# TY_FC_CONTRAL_9.net
KiCad netlist of a schematic drawn in EasyEDA Pro
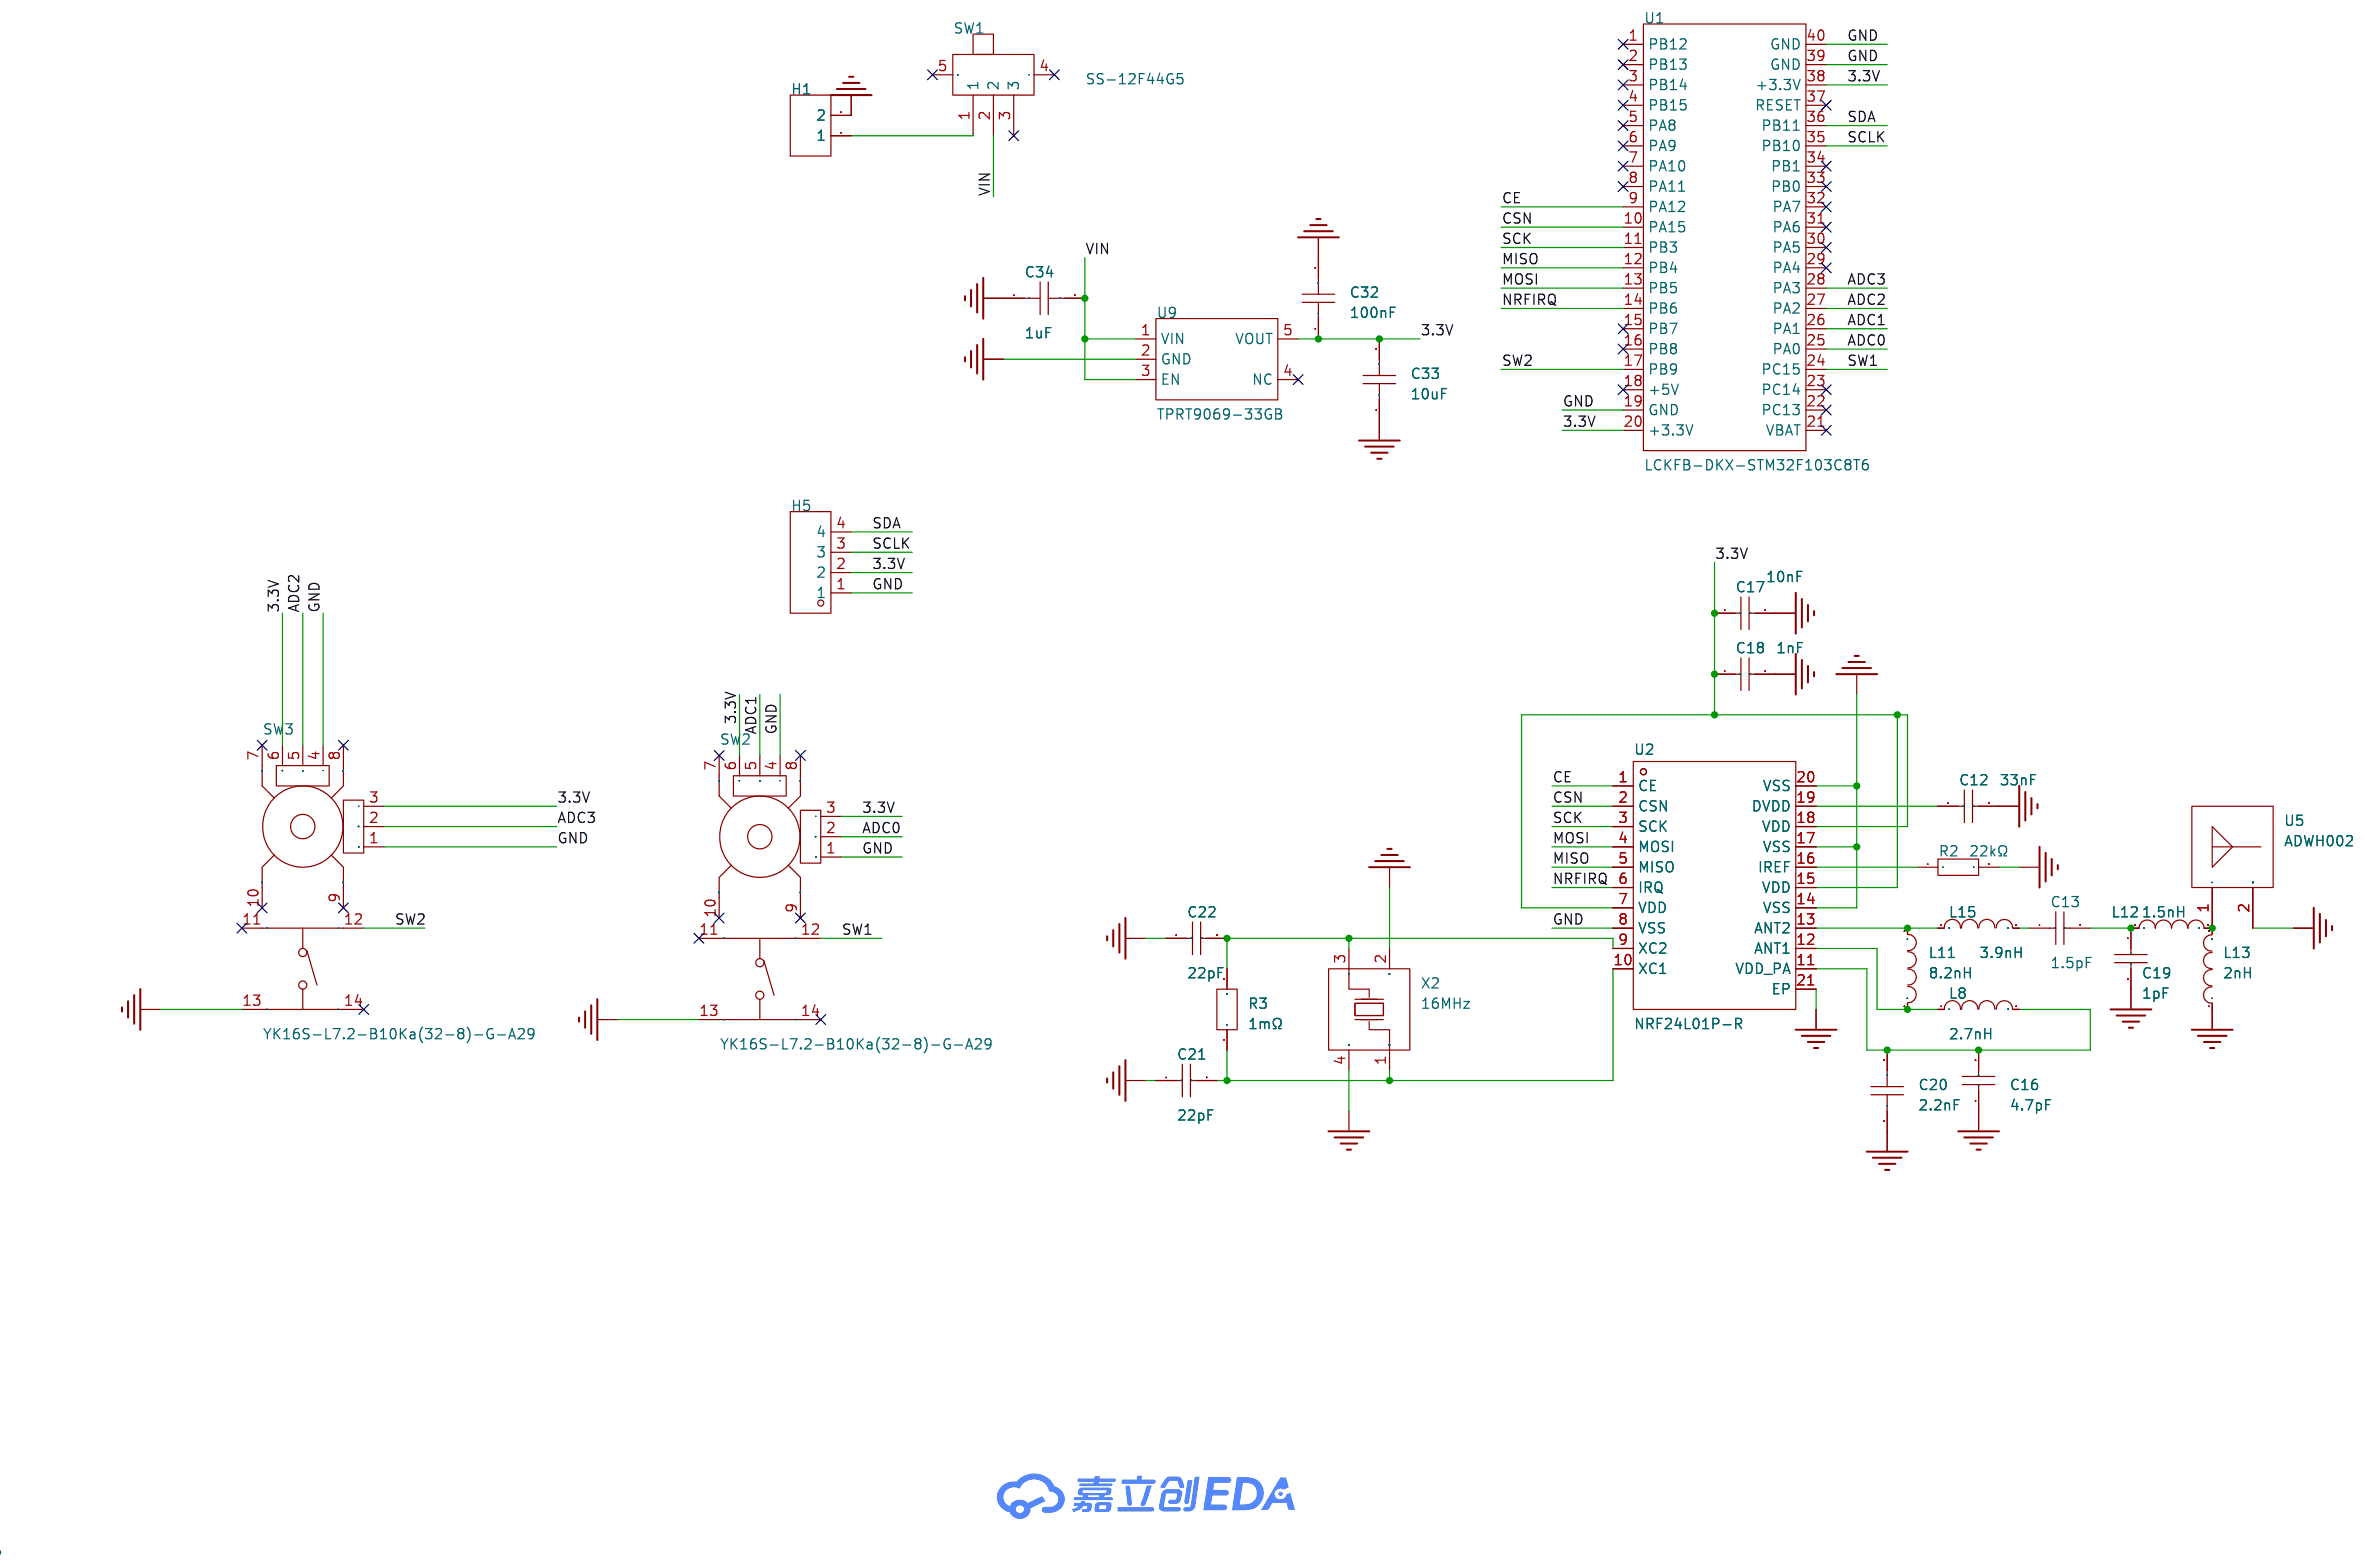
[diagram p0: schematic sheet]

(export (version "E")
  (design (tool "Eeschema 10.0.6"))
  (components
    (comp (ref "C12")
      (value "33nF")
      (footprint "easyedapro:C0603")
      (description "容值:33nF;精度:±10%;额定电压:50V;温度系数:X7R;")
      (fields
        (field (name "Manufacturer Part") "CL10B333KB8NNNC")
        (field (name "Manufacturer") "SAMSUNG(三星)")
      )
      (libsource (lib "easyedapro") (part "CL10B333KB8NNNC"))
    )
    (comp (ref "C13")
      (value "1.5pF")
      (footprint "easyedapro:C0603")
      (description "容值:1.5pF;额定电压:50V;温度系数:C0G;")
      (fields (field (name "Manufacturer Part") "0603CG1R5C500NT") (field (name "Manufacturer") "FH(风华)"))
      (libsource (lib "easyedapro") (part "0603CG1R5C500NT"))
    )
    (comp (ref "C16")
      (value "4.7pF")
      (footprint "easyedapro:C0603")
      (description "容值:4.7pF;额定电压:50V;温度系数:C0G;")
      (fields (field (name "Manufacturer Part") "0603CG4R7C500NT") (field (name "Manufacturer") "FH(风华)"))
      (libsource (lib "easyedapro") (part "0603CG4R7C500NT"))
    )
    (comp (ref "C17")
      (value "10nF")
      (footprint "easyedapro:C0603")
      (description "容值:10nF;精度:±10%;额定电压:50V;温度系数:X7R;")
      (fields
        (field (name "Manufacturer Part") "CC0603KRX7R9BB103")
        (field (name "Manufacturer") "YAGEO(国巨)")
      )
      (libsource (lib "easyedapro") (part "CC0603KRX7R9BB103"))
    )
    (comp (ref "C18")
      (value "1nF")
      (footprint "easyedapro:C0603")
      (description "容值:1nF;精度:±10%;额定电压:50V;温度系数:X7R;")
      (fields
        (field (name "Manufacturer Part") "CL10B102KB8NNNC")
        (field (name "Manufacturer") "SAMSUNG(三星)")
      )
      (libsource (lib "easyedapro") (part "CL10B102KB8NNNC"))
    )
    (comp (ref "C19")
      (value "1pF")
      (footprint "easyedapro:C0603")
      (description "容值:1pF;额定电压:50V;温度系数:C0G;")
      (fields (field (name "Manufacturer Part") "0603CG1R0C500NT") (field (name "Manufacturer") "FH(风华)"))
      (libsource (lib "easyedapro") (part "0603CG1R0C500NT_C37117"))
    )
    (comp (ref "C20")
      (value "2.2nF")
      (footprint "easyedapro:C0603")
      (description "容值:2.2nF;精度:±10%;额定电压:50V;温度系数:X7R;")
      (fields
        (field (name "Manufacturer Part") "FCC0603B222K500CT")
        (field (name "Manufacturer") "FOJAN(富捷)")
      )
      (libsource (lib "easyedapro") (part "FCC0603B222K500CT"))
    )
    (comp (ref "C21")
      (value "22pF")
      (footprint "easyedapro:C0603")
      (description "容值:22pF;精度:±5%;额定电压:50V;温度系数:C0G;")
      (fields
        (field (name "Manufacturer Part") "CL10C220JB8NNNC")
        (field (name "Manufacturer") "SAMSUNG(三星)")
      )
      (libsource (lib "easyedapro") (part "CL10C220JB8NNNC"))
    )
    (comp (ref "C22")
      (value "22pF")
      (footprint "easyedapro:C0603")
      (description "容值:22pF;精度:±5%;额定电压:50V;温度系数:C0G;")
      (fields
        (field (name "Manufacturer Part") "CL10C220JB8NNNC")
        (field (name "Manufacturer") "SAMSUNG(三星)")
      )
      (libsource (lib "easyedapro") (part "CL10C220JB8NNNC"))
    )
    (comp (ref "C32")
      (value "100nF")
      (footprint "easyedapro:C0603")
      (description "容值:100nF;精度:±10%;额定电压:50V;温度系数:X7R;")
      (fields
        (field (name "Manufacturer Part") "CC0603KRX7R9BB104")
        (field (name "Manufacturer") "YAGEO(国巨)")
      )
      (libsource (lib "easyedapro") (part "CC0603KRX7R9BB104"))
    )
    (comp (ref "C33")
      (value "10uF")
      (footprint "easyedapro:C0603")
      (description "容值:10uF;精度:±10%;额定电压:10V;温度系数:X5R;")
      (fields
        (field (name "Manufacturer Part") "CGA0603X5R106K100JT")
        (field (name "Manufacturer") "HRE(芯声)")
      )
      (libsource (lib "easyedapro") (part "CGA0603X5R106K100JT"))
    )
    (comp (ref "C34")
      (value "1uF")
      (footprint "easyedapro:C0603")
      (description "容值:1uF;精度:±10%;额定电压:50V;温度系数:X5R;")
      (fields
        (field (name "Manufacturer Part") "CGA0603X5R105K500JT")
        (field (name "Manufacturer") "HRE(芯声)")
      )
      (libsource (lib "easyedapro") (part "CGA0603X5R105K500JT"))
    )
    (comp (ref "H1")
      (value "~")
      (footprint "easyedapro:HDR-TH_2P-P2.54-V-F")
      (libsource (lib "easyedapro") (part "Header-Female-2.54_1x2"))
    )
    (comp (ref "H5")
      (value "~")
      (footprint "easyedapro:HDR-TH_4P-P2.54-V-F")
      (libsource (lib "easyedapro") (part "2.54-1*4P母"))
    )
    (comp (ref "L8")
      (value "2.7nH")
      (footprint "easyedapro:L0402")
      (description "电感值:2.7nH;精度:-;额定电流:800mA;饱和电流(Isat):-;直流电阻(DCR):120mΩ;")
      (fields (field (name "Manufacturer Part") "LQG15HS2N7S02D") (field (name "Manufacturer") "muRata(村田)"))
      (libsource (lib "easyedapro") (part "LQG15HS2N7S02D"))
    )
    (comp (ref "L11")
      (value "8.2nH")
      (footprint "easyedapro:L0402")
      (description "电感值:8.2nH;精度:±5%;额定电流:300mA;饱和电流(Isat):-;直流电阻(DCR):400mΩ;")
      (fields
        (field (name "Manufacturer Part") "SDCL1005C8N2JTDF")
        (field (name "Manufacturer") "Sunlord(顺络)")
      )
      (libsource (lib "easyedapro") (part "SDCL1005C8N2JTDF"))
    )
    (comp (ref "L12")
      (value "1.5nH")
      (footprint "easyedapro:L0603")
      (description "电感值:1.5nH;精度:-;额定电流:1.1A;饱和电流(Isat):-;直流电阻(DCR):100mΩ;")
      (fields (field (name "Manufacturer Part") "LQG18HN1N5S00D") (field (name "Manufacturer") "muRata(村田)"))
      (libsource (lib "easyedapro") (part "LQG18HN1N5S00D"))
    )
    (comp (ref "L13")
      (value "2nH")
      (footprint "easyedapro:L0603")
      (description "电感值:2nH;额定电流:-;饱和电流(Isat):-;直流电阻(DCR):-;")
      (fields
        (field (name "Manufacturer Part") "SDCL1608C2N0STDF")
        (field (name "Manufacturer") "Sunlord(顺络)")
      )
      (libsource (lib "easyedapro") (part "SDCL1608C2N0STDF_C370234"))
    )
    (comp (ref "L15")
      (value "3.9nH")
      (footprint "easyedapro:L0402")
      (description "电感值:3.9nH;精度:-;额定电流:300mA;饱和电流(Isat):-;直流电阻(DCR):200mΩ;")
      (fields
        (field (name "Manufacturer Part") "SDCL1005C3N9STDF")
        (field (name "Manufacturer") "Sunlord(顺络)")
      )
      (libsource (lib "easyedapro") (part "SDCL1005C3N9STDF"))
    )
    (comp (ref "R2")
      (value "22kΩ")
      (footprint "easyedapro:R0603")
      (description "电阻类型:厚膜电阻;阻值:22kΩ;精度:±1%;功率:100mW;工作电压:75V;温度系数:±100ppm/°C;")
      (fields
        (field (name "Manufacturer Part") "0603WAF2202T5E")
        (field (name "Manufacturer") "UNI-ROYAL(厚声)")
      )
      (libsource (lib "easyedapro") (part "0603WAF2202T5E"))
    )
    (comp (ref "R3")
      (value "1mΩ")
      (footprint "easyedapro:R0603")
      (description "电阻类型:-;阻值:1mΩ;精度:±1%;功率:100mW;温度系数:±300ppm/°C;")
      (fields
        (field (name "Manufacturer Part") "PA0603FRP070R001L")
        (field (name "Manufacturer") "YAGEO(国巨)")
      )
      (libsource (lib "easyedapro") (part "PA0603FRP070R001L"))
    )
    (comp (ref "SW1")
      (value "SS-12F44G5")
      (footprint "easyedapro:SW-TH_SS-12F44G5")
      (description "操作正拨 插件立式 尺寸大型 两档位")
      (fields (field (name "Manufacturer") "SOFNG(硕方)"))
      (libsource (lib "easyedapro") (part "SS-12F44G5"))
    )
    (comp (ref "SW2")
      (value "YK16S-L7.2-B10Ka(32-8)-G-A29")
      (footprint "easyedapro:JOYTICK-TH_YF16S-FL7.2-B5KB-45-10-Y_1")
      (description "摇杆电位器、操纵杆电位器，适用于航模玩具遥控器电位器、3D摇杆PS4手柄游戏机、无人机摇杆电位器、VR摇杆电位器、工业控制器")
      (fields (field (name "Manufacturer") "YTL(亚特联)"))
      (libsource (lib "easyedapro") (part "THB001P"))
    )
    (comp (ref "SW3")
      (value "YK16S-L7.2-B10Ka(32-8)-G-A29")
      (footprint "easyedapro:JOYTICK-TH_YF16S-FL7.2-B5KB-45-10-Y_1")
      (description "摇杆电位器、操纵杆电位器，适用于航模玩具遥控器电位器、3D摇杆PS4手柄游戏机、无人机摇杆电位器、VR摇杆电位器、工业控制器")
      (fields (field (name "Manufacturer") "YTL(亚特联)"))
      (libsource (lib "easyedapro") (part "THB001P"))
    )
    (comp (ref "U1")
      (value "LCKFB-DKX-STM32F103C8T6")
      (footprint "easyedapro:CONN-TH_L53.3-W22.9_STM32F103C8T6-CARD")
      (description "搭载Contex M3内核,程序存储容量64KB,RAM总容量20KB,最高72MHz主频,提供高效的计算能力和稳定的运行环境。")
      (fields (field (name "Manufacturer") "立创开发板"))
      (libsource (lib "easyedapro") (part "LCKFB-DKX-STM32F103C8T6"))
    )
    (comp (ref "U2")
      (value "NRF24L01P-R")
      (footprint "easyedapro:QFN-20_L4.0-W4.0-P0.50-BL-EP")
      (description "频率范围:2.4GHz~2.525GHz;接口类型:SPI;应用领域:ISM;数据速率:2Mbps;灵敏度:-82dBm;典型应用频率:2.4GHz;")
      (fields (field (name "Manufacturer") "NORDIC"))
      (libsource (lib "easyedapro") (part "NRF24L01P-R"))
    )
    (comp (ref "U5")
      (value "ADWH002")
      (footprint "easyedapro:ANT-SMD_L5.0-W2.0_HM5B")
      (description "天线类型:-;中心频率:2.45GHz;带宽:100MHz;增益:0.67dBi;功率:3W;驻波比:2;")
      (fields (field (name "Manufacturer") "MyAntenna(摩天射频)"))
      (libsource (lib "easyedapro") (part "ADWH002"))
    )
    (comp (ref "U9")
      (value "TPRT9069-33GB")
      (footprint "easyedapro:SOT-23-5_L3.0-W1.7-P0.95-LS2.8-BR")
      (description "输出类型:固定;工作电压:36V;输出电压:3.3V;输出电流:200mA;电源纹波抑制比(PSRR):70dB@(100Hz);输出极性:正极;")
      (fields (field (name "Manufacturer") "TECH PUBLIC(台舟)"))
      (libsource (lib "easyedapro") (part "TPRT9069-33GB"))
    )
    (comp (ref "X2")
      (value "16MHz")
      (footprint "easyedapro:OSC-SMD_4P-L3.2-W2.5-BL")
      (description "晶振类型:贴片晶振;频率:16MHz;常温频差:±10ppm;负载电容:9pF;频率稳定度:±20ppm;")
      (fields (field (name "Manufacturer Part") "X322516MLB4SI") (field (name "Manufacturer") "YXC(扬兴晶振)"))
      (libsource (lib "easyedapro") (part "X322516MLB4SI"))
    )
  )
  (nets
    (net (code "1") (name "/3.3V") (class "Default")
      (node (ref "C17") (pin "1") (pinfunction "1_1") (pintype "input"))
      (node (ref "C18") (pin "1") (pinfunction "1_1") (pintype "input"))
      (node (ref "C32") (pin "1") (pinfunction "1_1") (pintype "unspecified"))
      (node (ref "C33") (pin "2") (pinfunction "2_2") (pintype "unspecified"))
      (node (ref "H5") (pin "2") (pinfunction "2_2") (pintype "unspecified"))
      (node (ref "SW2") (pin "3") (pinfunction "A_3") (pintype "unspecified"))
      (node (ref "SW2") (pin "6") (pinfunction "B_6") (pintype "unspecified"))
      (node (ref "SW3") (pin "3") (pinfunction "A_3") (pintype "unspecified"))
      (node (ref "SW3") (pin "6") (pinfunction "B_6") (pintype "unspecified"))
      (node (ref "U1") (pin "20") (pinfunction "+3.3V_20") (pintype "unspecified"))
      (node (ref "U1") (pin "38") (pinfunction "+3.3V_38") (pintype "unspecified"))
      (node (ref "U2") (pin "15") (pinfunction "VDD_15") (pintype "unspecified"))
      (node (ref "U2") (pin "18") (pinfunction "VDD_18") (pintype "unspecified"))
      (node (ref "U2") (pin "7") (pinfunction "VDD_7") (pintype "unspecified"))
      (node (ref "U9") (pin "5") (pinfunction "VOUT_5") (pintype "unspecified"))
    )
    (net (code "2") (name "/ADC0") (class "Default")
      (node (ref "SW2") (pin "2") (pinfunction "DTA_2") (pintype "unspecified"))
      (node (ref "U1") (pin "25") (pinfunction "PA0_25") (pintype "unspecified"))
    )
    (net (code "3") (name "/ADC1") (class "Default")
      (node (ref "SW2") (pin "5") (pinfunction "DTA_5") (pintype "unspecified"))
      (node (ref "U1") (pin "26") (pinfunction "PA1_26") (pintype "unspecified"))
    )
    (net (code "4") (name "/ADC2") (class "Default")
      (node (ref "SW3") (pin "5") (pinfunction "DTA_5") (pintype "unspecified"))
      (node (ref "U1") (pin "27") (pinfunction "PA2_27") (pintype "unspecified"))
    )
    (net (code "5") (name "/ADC3") (class "Default")
      (node (ref "SW3") (pin "2") (pinfunction "DTA_2") (pintype "unspecified"))
      (node (ref "U1") (pin "28") (pinfunction "PA3_28") (pintype "unspecified"))
    )
    (net (code "6") (name "/CE") (class "Default")
      (node (ref "U1") (pin "9") (pinfunction "PA12_9") (pintype "unspecified"))
      (node (ref "U2") (pin "1") (pinfunction "CE_1") (pintype "unspecified"))
    )
    (net (code "7") (name "/CSN") (class "Default")
      (node (ref "U1") (pin "10") (pinfunction "PA15_10") (pintype "unspecified"))
      (node (ref "U2") (pin "2") (pinfunction "CSN_2") (pintype "unspecified"))
    )
    (net (code "8") (name "/MISO") (class "Default")
      (node (ref "U1") (pin "12") (pinfunction "PB4_12") (pintype "unspecified"))
      (node (ref "U2") (pin "5") (pinfunction "MISO_5") (pintype "unspecified"))
    )
    (net (code "9") (name "/MOSI") (class "Default")
      (node (ref "U1") (pin "13") (pinfunction "PB5_13") (pintype "unspecified"))
      (node (ref "U2") (pin "4") (pinfunction "MOSI_4") (pintype "unspecified"))
    )
    (net (code "10") (name "/NRFIRQ") (class "Default")
      (node (ref "U1") (pin "14") (pinfunction "PB6_14") (pintype "unspecified"))
      (node (ref "U2") (pin "6") (pinfunction "IRQ_6") (pintype "unspecified"))
    )
    (net (code "11") (name "/SCK") (class "Default")
      (node (ref "U1") (pin "11") (pinfunction "PB3_11") (pintype "unspecified"))
      (node (ref "U2") (pin "3") (pinfunction "SCK_3") (pintype "unspecified"))
    )
    (net (code "12") (name "/SCLK") (class "Default")
      (node (ref "H5") (pin "3") (pinfunction "3_3") (pintype "unspecified"))
      (node (ref "U1") (pin "35") (pinfunction "PB10_35") (pintype "unspecified"))
    )
    (net (code "13") (name "/SDA") (class "Default")
      (node (ref "H5") (pin "4") (pinfunction "4_4") (pintype "unspecified"))
      (node (ref "U1") (pin "36") (pinfunction "PB11_36") (pintype "unspecified"))
    )
    (net (code "14") (name "/SW1") (class "Default")
      (node (ref "SW2") (pin "12") (pinfunction "b_12") (pintype "unspecified"))
      (node (ref "U1") (pin "24") (pinfunction "PC15_24") (pintype "unspecified"))
    )
    (net (code "15") (name "/SW2") (class "Default")
      (node (ref "SW3") (pin "12") (pinfunction "b_12") (pintype "unspecified"))
      (node (ref "U1") (pin "17") (pinfunction "PB9_17") (pintype "unspecified"))
    )
    (net (code "16") (name "/VIN") (class "Default")
      (node (ref "C34") (pin "2") (pinfunction "2_2") (pintype "unspecified"))
      (node (ref "SW1") (pin "2") (pinfunction "2_2") (pintype "unspecified"))
      (node (ref "U9") (pin "1") (pinfunction "VIN_1") (pintype "unspecified"))
      (node (ref "U9") (pin "3") (pinfunction "EN_3") (pintype "unspecified"))
    )
    (net (code "17") (name "GND") (class "Default")
      (node (ref "C12") (pin "2") (pinfunction "2_2") (pintype "input"))
      (node (ref "C16") (pin "1") (pinfunction "1_1") (pintype "input"))
      (node (ref "C17") (pin "2") (pinfunction "2_2") (pintype "input"))
      (node (ref "C18") (pin "2") (pinfunction "2_2") (pintype "input"))
      (node (ref "C19") (pin "2") (pinfunction "2_2") (pintype "input"))
      (node (ref "C20") (pin "1") (pinfunction "1_1") (pintype "unspecified"))
      (node (ref "C21") (pin "1") (pinfunction "1_1") (pintype "input"))
      (node (ref "C22") (pin "1") (pinfunction "1_1") (pintype "input"))
      (node (ref "C32") (pin "2") (pinfunction "2_2") (pintype "unspecified"))
      (node (ref "C33") (pin "1") (pinfunction "1_1") (pintype "unspecified"))
      (node (ref "C34") (pin "1") (pinfunction "1_1") (pintype "unspecified"))
      (node (ref "H1") (pin "2") (pinfunction "2_2") (pintype "input"))
      (node (ref "H5") (pin "1") (pinfunction "1_1") (pintype "unspecified"))
      (node (ref "L13") (pin "1") (pinfunction "1_1") (pintype "unspecified"))
      (node (ref "R2") (pin "2") (pinfunction "2_2") (pintype "input"))
      (node (ref "SW2") (pin "1") (pinfunction "B_1") (pintype "unspecified"))
      (node (ref "SW2") (pin "13") (pinfunction "c_13") (pintype "unspecified"))
      (node (ref "SW2") (pin "4") (pinfunction "A_4") (pintype "unspecified"))
      (node (ref "SW3") (pin "1") (pinfunction "B_1") (pintype "unspecified"))
      (node (ref "SW3") (pin "13") (pinfunction "c_13") (pintype "unspecified"))
      (node (ref "SW3") (pin "4") (pinfunction "A_4") (pintype "unspecified"))
      (node (ref "U1") (pin "19") (pinfunction "GND_19") (pintype "unspecified"))
      (node (ref "U1") (pin "39") (pinfunction "GND_39") (pintype "unspecified"))
      (node (ref "U1") (pin "40") (pinfunction "GND_40") (pintype "unspecified"))
      (node (ref "U2") (pin "14") (pinfunction "VSS_14") (pintype "unspecified"))
      (node (ref "U2") (pin "17") (pinfunction "VSS_17") (pintype "unspecified"))
      (node (ref "U2") (pin "20") (pinfunction "VSS_20") (pintype "unspecified"))
      (node (ref "U2") (pin "21") (pinfunction "EP_21") (pintype "unspecified"))
      (node (ref "U2") (pin "8") (pinfunction "VSS_8") (pintype "unspecified"))
      (node (ref "U5") (pin "2") (pinfunction "GND_2") (pintype "unspecified"))
      (node (ref "U9") (pin "2") (pinfunction "GND_2") (pintype "unspecified"))
      (node (ref "X2") (pin "2") (pinfunction "GND_2") (pintype "unspecified"))
      (node (ref "X2") (pin "4") (pinfunction "GND_4") (pintype "unspecified"))
    )
    (net (code "18") (name "Net-(C13-Pad1)") (class "Default")
      (node (ref "C13") (pin "1") (pinfunction "1_1") (pintype "input"))
      (node (ref "L15") (pin "2") (pinfunction "2_2") (pintype "unspecified"))
    )
    (net (code "19") (name "Net-(C13-Pad2)") (class "Default")
      (node (ref "C13") (pin "2") (pinfunction "2_2") (pintype "input"))
      (node (ref "C19") (pin "1") (pinfunction "1_1") (pintype "input"))
      (node (ref "L12") (pin "1") (pinfunction "1_1") (pintype "unspecified"))
    )
    (net (code "20") (name "Net-(H1-Pad1)") (class "Default")
      (node (ref "H1") (pin "1") (pinfunction "1_1") (pintype "input"))
      (node (ref "SW1") (pin "1") (pinfunction "1_1") (pintype "unspecified"))
    )
    (net (code "21") (name "Net-(U2-ANT1)") (class "Default")
      (node (ref "L11") (pin "2") (pinfunction "2_2") (pintype "unspecified"))
      (node (ref "L8") (pin "1") (pinfunction "1_1") (pintype "unspecified"))
      (node (ref "U2") (pin "12") (pinfunction "ANT1_12") (pintype "unspecified"))
    )
    (net (code "22") (name "Net-(U2-ANT2)") (class "Default")
      (node (ref "L11") (pin "1") (pinfunction "1_1") (pintype "unspecified"))
      (node (ref "L15") (pin "1") (pinfunction "1_1") (pintype "unspecified"))
      (node (ref "U2") (pin "13") (pinfunction "ANT2_13") (pintype "unspecified"))
    )
    (net (code "23") (name "Net-(U2-DVDD)") (class "Default")
      (node (ref "C12") (pin "1") (pinfunction "1_1") (pintype "input"))
      (node (ref "U2") (pin "19") (pinfunction "DVDD_19") (pintype "unspecified"))
    )
    (net (code "24") (name "Net-(U2-IREF)") (class "Default")
      (node (ref "R2") (pin "1") (pinfunction "1_1") (pintype "input"))
      (node (ref "U2") (pin "16") (pinfunction "IREF_16") (pintype "unspecified"))
    )
    (net (code "25") (name "Net-(U2-VDD_PA)") (class "Default")
      (node (ref "C16") (pin "2") (pinfunction "2_2") (pintype "input"))
      (node (ref "C20") (pin "2") (pinfunction "2_2") (pintype "unspecified"))
      (node (ref "L8") (pin "2") (pinfunction "2_2") (pintype "unspecified"))
      (node (ref "U2") (pin "11") (pinfunction "VDD_PA_11") (pintype "unspecified"))
    )
    (net (code "26") (name "Net-(U2-XC1)") (class "Default")
      (node (ref "C21") (pin "2") (pinfunction "2_2") (pintype "input"))
      (node (ref "R3") (pin "1") (pinfunction "1_1") (pintype "unspecified"))
      (node (ref "U2") (pin "10") (pinfunction "XC1_10") (pintype "unspecified"))
      (node (ref "X2") (pin "1") (pinfunction "OSC1_1") (pintype "unspecified"))
    )
    (net (code "27") (name "Net-(U2-XC2)") (class "Default")
      (node (ref "C22") (pin "2") (pinfunction "2_2") (pintype "input"))
      (node (ref "R3") (pin "2") (pinfunction "2_2") (pintype "unspecified"))
      (node (ref "U2") (pin "9") (pinfunction "XC2_9") (pintype "unspecified"))
      (node (ref "X2") (pin "3") (pinfunction "OSC2_3") (pintype "unspecified"))
    )
    (net (code "28") (name "Net-(U5-IN)") (class "Default")
      (node (ref "L12") (pin "2") (pinfunction "2_2") (pintype "unspecified"))
      (node (ref "L13") (pin "2") (pinfunction "2_2") (pintype "unspecified"))
      (node (ref "U5") (pin "1") (pinfunction "IN_1") (pintype "unspecified"))
    )
    (net (code "29") (name "unconnected-(SW1-Pad3)") (class "Default")
      (node (ref "SW1") (pin "3") (pinfunction "3_3") (pintype "unspecified+no_connect"))
    )
    (net (code "30") (name "unconnected-(SW1-Pad4)") (class "Default")
      (node (ref "SW1") (pin "4") (pinfunction "4_4") (pintype "unspecified+no_connect"))
    )
    (net (code "31") (name "unconnected-(SW1-Pad5)") (class "Default")
      (node (ref "SW1") (pin "5") (pinfunction "5_5") (pintype "unspecified+no_connect"))
    )
    (net (code "32") (name "unconnected-(SW2-GND-Pad7)") (class "Default")
      (node (ref "SW2") (pin "7") (pinfunction "GND_7") (pintype "unspecified+no_connect"))
    )
    (net (code "33") (name "unconnected-(SW2-GND-Pad8)") (class "Default")
      (node (ref "SW2") (pin "8") (pinfunction "GND_8") (pintype "unspecified+no_connect"))
    )
    (net (code "34") (name "unconnected-(SW2-GND-Pad9)") (class "Default")
      (node (ref "SW2") (pin "9") (pinfunction "GND_9") (pintype "unspecified+no_connect"))
    )
    (net (code "35") (name "unconnected-(SW2-GND-Pad10)") (class "Default")
      (node (ref "SW2") (pin "10") (pinfunction "GND_10") (pintype "unspecified+no_connect"))
    )
    (net (code "36") (name "unconnected-(SW2-a-Pad11)") (class "Default")
      (node (ref "SW2") (pin "11") (pinfunction "a_11") (pintype "unspecified+no_connect"))
    )
    (net (code "37") (name "unconnected-(SW2-d-Pad14)") (class "Default")
      (node (ref "SW2") (pin "14") (pinfunction "d_14") (pintype "unspecified+no_connect"))
    )
    (net (code "38") (name "unconnected-(SW3-GND-Pad7)") (class "Default")
      (node (ref "SW3") (pin "7") (pinfunction "GND_7") (pintype "unspecified+no_connect"))
    )
    (net (code "39") (name "unconnected-(SW3-GND-Pad8)") (class "Default")
      (node (ref "SW3") (pin "8") (pinfunction "GND_8") (pintype "unspecified+no_connect"))
    )
    (net (code "40") (name "unconnected-(SW3-GND-Pad9)") (class "Default")
      (node (ref "SW3") (pin "9") (pinfunction "GND_9") (pintype "unspecified+no_connect"))
    )
    (net (code "41") (name "unconnected-(SW3-GND-Pad10)") (class "Default")
      (node (ref "SW3") (pin "10") (pinfunction "GND_10") (pintype "unspecified+no_connect"))
    )
    (net (code "42") (name "unconnected-(SW3-a-Pad11)") (class "Default")
      (node (ref "SW3") (pin "11") (pinfunction "a_11") (pintype "unspecified+no_connect"))
    )
    (net (code "43") (name "unconnected-(SW3-d-Pad14)") (class "Default")
      (node (ref "SW3") (pin "14") (pinfunction "d_14") (pintype "unspecified+no_connect"))
    )
    (net (code "44") (name "unconnected-(U1-+5V-Pad18)") (class "Default")
      (node (ref "U1") (pin "18") (pinfunction "+5V_18") (pintype "unspecified+no_connect"))
    )
    (net (code "45") (name "unconnected-(U1-PA4-Pad29)") (class "Default")
      (node (ref "U1") (pin "29") (pinfunction "PA4_29") (pintype "unspecified+no_connect"))
    )
    (net (code "46") (name "unconnected-(U1-PA5-Pad30)") (class "Default")
      (node (ref "U1") (pin "30") (pinfunction "PA5_30") (pintype "unspecified+no_connect"))
    )
    (net (code "47") (name "unconnected-(U1-PA6-Pad31)") (class "Default")
      (node (ref "U1") (pin "31") (pinfunction "PA6_31") (pintype "unspecified+no_connect"))
    )
    (net (code "48") (name "unconnected-(U1-PA7-Pad32)") (class "Default")
      (node (ref "U1") (pin "32") (pinfunction "PA7_32") (pintype "unspecified+no_connect"))
    )
    (net (code "49") (name "unconnected-(U1-PA8-Pad5)") (class "Default")
      (node (ref "U1") (pin "5") (pinfunction "PA8_5") (pintype "unspecified+no_connect"))
    )
    (net (code "50") (name "unconnected-(U1-PA9-Pad6)") (class "Default")
      (node (ref "U1") (pin "6") (pinfunction "PA9_6") (pintype "unspecified+no_connect"))
    )
    (net (code "51") (name "unconnected-(U1-PA10-Pad7)") (class "Default")
      (node (ref "U1") (pin "7") (pinfunction "PA10_7") (pintype "unspecified+no_connect"))
    )
    (net (code "52") (name "unconnected-(U1-PA11-Pad8)") (class "Default")
      (node (ref "U1") (pin "8") (pinfunction "PA11_8") (pintype "unspecified+no_connect"))
    )
    (net (code "53") (name "unconnected-(U1-PB0-Pad33)") (class "Default")
      (node (ref "U1") (pin "33") (pinfunction "PB0_33") (pintype "unspecified+no_connect"))
    )
    (net (code "54") (name "unconnected-(U1-PB1-Pad34)") (class "Default")
      (node (ref "U1") (pin "34") (pinfunction "PB1_34") (pintype "unspecified+no_connect"))
    )
    (net (code "55") (name "unconnected-(U1-PB7-Pad15)") (class "Default")
      (node (ref "U1") (pin "15") (pinfunction "PB7_15") (pintype "unspecified+no_connect"))
    )
    (net (code "56") (name "unconnected-(U1-PB8-Pad16)") (class "Default")
      (node (ref "U1") (pin "16") (pinfunction "PB8_16") (pintype "unspecified+no_connect"))
    )
    (net (code "57") (name "unconnected-(U1-PB12-Pad1)") (class "Default")
      (node (ref "U1") (pin "1") (pinfunction "PB12_1") (pintype "unspecified+no_connect"))
    )
    (net (code "58") (name "unconnected-(U1-PB13-Pad2)") (class "Default")
      (node (ref "U1") (pin "2") (pinfunction "PB13_2") (pintype "unspecified+no_connect"))
    )
    (net (code "59") (name "unconnected-(U1-PB14-Pad3)") (class "Default")
      (node (ref "U1") (pin "3") (pinfunction "PB14_3") (pintype "unspecified+no_connect"))
    )
    (net (code "60") (name "unconnected-(U1-PB15-Pad4)") (class "Default")
      (node (ref "U1") (pin "4") (pinfunction "PB15_4") (pintype "unspecified+no_connect"))
    )
    (net (code "61") (name "unconnected-(U1-PC13-Pad22)") (class "Default")
      (node (ref "U1") (pin "22") (pinfunction "PC13_22") (pintype "unspecified+no_connect"))
    )
    (net (code "62") (name "unconnected-(U1-PC14-Pad23)") (class "Default")
      (node (ref "U1") (pin "23") (pinfunction "PC14_23") (pintype "unspecified+no_connect"))
    )
    (net (code "63") (name "unconnected-(U1-RESET-Pad37)") (class "Default")
      (node (ref "U1") (pin "37") (pinfunction "RESET_37") (pintype "unspecified+no_connect"))
    )
    (net (code "64") (name "unconnected-(U1-VBAT-Pad21)") (class "Default")
      (node (ref "U1") (pin "21") (pinfunction "VBAT_21") (pintype "unspecified+no_connect"))
    )
    (net (code "65") (name "unconnected-(U9-NC-Pad4)") (class "Default")
      (node (ref "U9") (pin "4") (pinfunction "NC_4") (pintype "unspecified+no_connect"))
    )
  )
)
